# Aeolus_SMA_inc_sensor.net
KiCad netlist of a schematic drawn in EAGLE
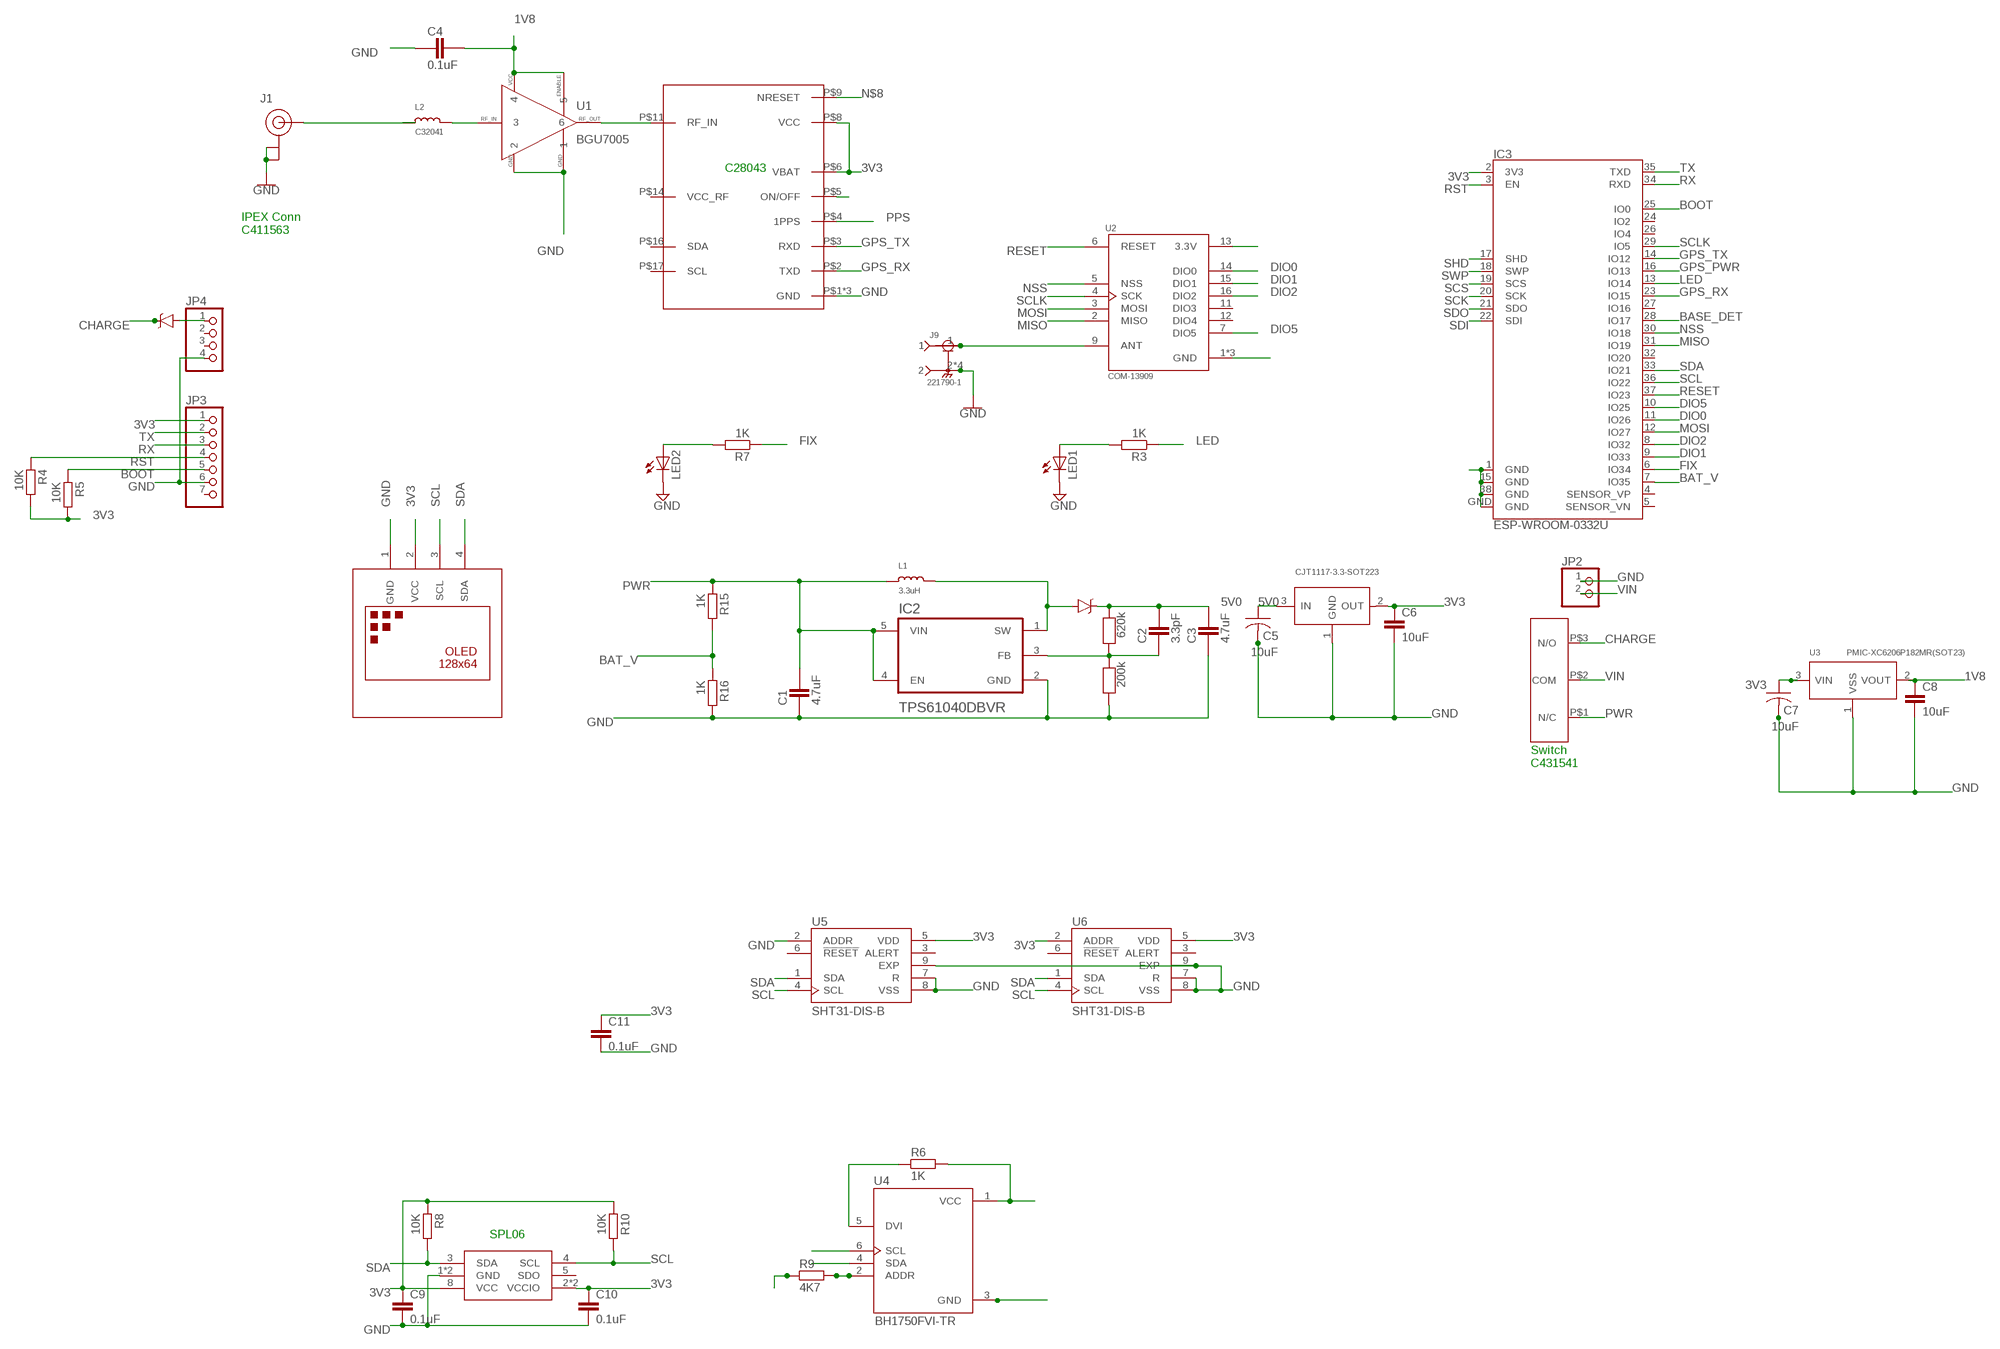
[diagram p0: schematic, sheet 1]

(export (version "E")
  (design (tool "Eeschema 10.0.6"))
  (components
    (comp (ref "C1")
      (value "4.7uF")
      (footprint "eagle-import:CAPC1608X92N")
      (libsource (lib "eagle-import") (part "CAPACITOR_0603"))
    )
    (comp (ref "C2")
      (value "3.3pF")
      (footprint "eagle-import:CAPC1005X60N")
      (libsource (lib "eagle-import") (part "CAPACITOR_0402"))
    )
    (comp (ref "C3")
      (value "4.7uF")
      (footprint "eagle-import:CAPC1608X92N")
      (libsource (lib "eagle-import") (part "CAPACITOR_0603"))
    )
    (comp (ref "C4")
      (value "0.1uF")
      (footprint "eagle-import:CAPC1608X92N")
      (libsource (lib "eagle-import") (part "CAPACITOR_0603"))
    )
    (comp (ref "C5")
      (value "10uF")
      (footprint "eagle-import:C0805")
      (libsource (lib "eagle-import") (part "C-USC0805"))
    )
    (comp (ref "C6")
      (value "10uF")
      (footprint "eagle-import:C0805@1")
      (libsource (lib "eagle-import") (part "C-EUC0805"))
    )
    (comp (ref "C7")
      (value "10uF")
      (footprint "eagle-import:C0402")
      (libsource (lib "eagle-import") (part "C-USC0402"))
    )
    (comp (ref "C8")
      (value "10uF")
      (footprint "eagle-import:C0402K@1")
      (libsource (lib "eagle-import") (part "C-EUC0402K"))
    )
    (comp (ref "C9")
      (value "0.1uF")
      (footprint "eagle-import:C0603@1")
      (libsource (lib "eagle-import") (part "C-EUC0603"))
    )
    (comp (ref "C10")
      (value "0.1uF")
      (footprint "eagle-import:C0603@1")
      (libsource (lib "eagle-import") (part "C-EUC0603"))
    )
    (comp (ref "C11")
      (value "0.1uF")
      (footprint "eagle-import:C0603@1")
      (libsource (lib "eagle-import") (part "C-EUC0603"))
    )
    (comp (ref "D1")
      (value "BA340A")
      (footprint "eagle-import:SMA-DIODE")
      (libsource (lib "eagle-import") (part "B340A"))
    )
    (comp (ref "D2")
      (value "BA340A")
      (footprint "eagle-import:SMA-DIODE")
      (libsource (lib "eagle-import") (part "B340A"))
    )
    (comp (ref "IC1")
      (value "CJT1117-3.3-SOT223")
      (footprint "eagle-import:SOT-223")
      (fields (field (name "MPN") "CJT1117-3.3"))
      (libsource (lib "eagle-import") (part "PMIC-CJT1117-3.3(SOT223)"))
    )
    (comp (ref "IC2")
      (value "TPS61040DBVR")
      (footprint "eagle-import:SOT95P280X145-5N")
      (fields (field (name "MF") "Texas Instruments"))
      (libsource (lib "eagle-import") (part "TPS61040DBVR"))
    )
    (comp (ref "IC3")
      (value "ESP-WROOM-0332U")
      (footprint "eagle-import:ESP32-WROOM-32U")
      (libsource (lib "eagle-import") (part "ESP-WROOM-0332U"))
    )
    (comp (ref "IC54")
      (value "ATGM336H")
      (footprint "eagle-import:ATGM336H")
      (libsource (lib "eagle-import") (part "ATGM336H"))
    )
    (comp (ref "J1")
      (value "U.FL")
      (footprint "eagle-import:U.FL")
      (libsource (lib "eagle-import") (part "U.FL"))
    )
    (comp (ref "J9")
      (value "221790-1")
      (footprint "eagle-import:TE_221790-1")
      (fields (field (name "MF") "TE Connectivity"))
      (libsource (lib "eagle-import") (part "221790-1"))
    )
    (comp (ref "JP2")
      (value "HEADER-1X2ROUND")
      (footprint "eagle-import:1X02_ROUND")
      (libsource (lib "eagle-import") (part "HEADER-1X2ROUND"))
    )
    (comp (ref "JP3")
      (value "HEADER-1X7ROUND")
      (footprint "eagle-import:1X07_ROUND")
      (libsource (lib "eagle-import") (part "HEADER-1X7ROUND"))
    )
    (comp (ref "JP4")
      (value "HEADER-1X4ROUND")
      (footprint "eagle-import:1X04_ROUND")
      (libsource (lib "eagle-import") (part "HEADER-1X4ROUND"))
    )
    (comp (ref "L1")
      (value "3.3uH")
      (footprint "eagle-import:INDUCTOR_5X5MM_NR5040_NOTHERMALS")
      (libsource (lib "eagle-import") (part "INDUCTORNR5040"))
    )
    (comp (ref "L2")
      (value "C32041")
      (footprint "eagle-import:_0402")
      (libsource (lib "eagle-import") (part "INDUCTOR_0402"))
    )
    (comp (ref "LED1")
      (value "LEDSML0805")
      (footprint "eagle-import:SML0805")
      (libsource (lib "eagle-import") (part "LEDSML0805"))
    )
    (comp (ref "LED2")
      (value "LEDSML0805")
      (footprint "eagle-import:SML0805")
      (libsource (lib "eagle-import") (part "LEDSML0805"))
    )
    (comp (ref "R1")
      (value "620k")
      (footprint "eagle-import:0603")
      (libsource (lib "eagle-import") (part "RESISTOR0603"))
    )
    (comp (ref "R2")
      (value "200k")
      (footprint "eagle-import:0603")
      (libsource (lib "eagle-import") (part "RESISTOR0603"))
    )
    (comp (ref "R3")
      (value "1K")
      (footprint "eagle-import:RESC1608X55N")
      (libsource (lib "eagle-import") (part "RESISTOR_0603"))
    )
    (comp (ref "R4")
      (value "10K")
      (footprint "eagle-import:RESC1608X55N")
      (libsource (lib "eagle-import") (part "RESISTOR_0603"))
    )
    (comp (ref "R5")
      (value "10K")
      (footprint "eagle-import:RESC1608X55N")
      (libsource (lib "eagle-import") (part "RESISTOR_0603"))
    )
    (comp (ref "R6")
      (value "1K")
      (footprint "eagle-import:RESC1608X55N")
      (libsource (lib "eagle-import") (part "RESISTOR_0603"))
    )
    (comp (ref "R7")
      (value "1K")
      (footprint "eagle-import:RESC1608X55N")
      (libsource (lib "eagle-import") (part "RESISTOR_0603"))
    )
    (comp (ref "R8")
      (value "10K")
      (footprint "eagle-import:RESC1608X55N")
      (libsource (lib "eagle-import") (part "RESISTOR_0603"))
    )
    (comp (ref "R9")
      (value "4K7")
      (footprint "eagle-import:RESC1608X55N")
      (libsource (lib "eagle-import") (part "RESISTOR_0603"))
    )
    (comp (ref "R10")
      (value "10K")
      (footprint "eagle-import:RESC1608X55N")
      (libsource (lib "eagle-import") (part "RESISTOR_0603"))
    )
    (comp (ref "R15")
      (value "1K")
      (footprint "eagle-import:RESC1608X55N")
      (libsource (lib "eagle-import") (part "RESISTOR_0603"))
    )
    (comp (ref "R16")
      (value "1K")
      (footprint "eagle-import:RESC1608X55N")
      (libsource (lib "eagle-import") (part "RESISTOR_0603"))
    )
    (comp (ref "S1")
      (value "SMD-SWITCH")
      (footprint "eagle-import:SMD-SWITCH")
      (libsource (lib "eagle-import") (part "SMD-SWITCH"))
    )
    (comp (ref "U$1")
      (value "DISPLAY-OLED-128X64-I2C")
      (footprint "eagle-import:DISPLAY-OLED-128X64-I2C")
      (libsource (lib "eagle-import") (part "DISPLAY-OLED-128X64-I2C"))
    )
    (comp (ref "U$4")
      (value "SPL06")
      (footprint "eagle-import:SPL06")
      (libsource (lib "eagle-import") (part "SPL06"))
    )
    (comp (ref "U1")
      (value "BGU7005")
      (footprint "eagle-import:SOT886")
      (fields (field (name "MF") "NXP USA"))
      (libsource (lib "eagle-import") (part "BGU7005"))
    )
    (comp (ref "U2")
      (value "COM-13909")
      (footprint "eagle-import:MOD_COM-13909")
      (fields (field (name "MF") "HOPERF") (field (name "MP") "RFM69HCW-315S2"))
      (libsource (lib "eagle-import") (part "COM-13909"))
    )
    (comp (ref "U3")
      (value "PMIC-XC6206P182MR(SOT23)")
      (footprint "eagle-import:SOT-23")
      (fields (field (name "MF") "Torex") (field (name "MP") "XC6206P182MR"))
      (libsource (lib "eagle-import") (part "PMIC-XC6206P182MR(SOT23)"))
    )
    (comp (ref "U4")
      (value "BH1750FVI-TR")
      (footprint "eagle-import:XDCR_BH1750FVI-TR")
      (fields (field (name "MF") "ROHM Semiconductor"))
      (libsource (lib "eagle-import") (part "BH1750FVI-TR"))
    )
    (comp (ref "U5")
      (value "SHT31-DIS-B")
      (footprint "eagle-import:SON50P250X250X100-9N")
      (fields (field (name "MF") "Sensirion AG"))
      (libsource (lib "eagle-import") (part "SHT31-DIS-B"))
    )
    (comp (ref "U6")
      (value "SHT31-DIS-B")
      (footprint "eagle-import:SON50P250X250X100-9N")
      (fields (field (name "MF") "Sensirion AG"))
      (libsource (lib "eagle-import") (part "SHT31-DIS-B"))
    )
  )
  (nets
    (net (code "1") (name "/1V8") (class "Default")
      (node (ref "C4") (pin "2") (pinfunction "2_2") (pintype "passive"))
      (node (ref "C8") (pin "1") (pinfunction "1_1") (pintype "passive"))
      (node (ref "U1") (pin "4") (pinfunction "4_4") (pintype "bidirectional"))
      (node (ref "U1") (pin "5") (pinfunction "5_5") (pintype "bidirectional"))
      (node (ref "U3") (pin "2") (pinfunction "VOUT_2") (pintype "output"))
    )
    (net (code "2") (name "/3V3") (class "Default")
      (node (ref "C10") (pin "1") (pinfunction "1_1") (pintype "passive"))
      (node (ref "C11") (pin "1") (pinfunction "1_1") (pintype "passive"))
      (node (ref "C6") (pin "1") (pinfunction "1_1") (pintype "passive"))
      (node (ref "C7") (pin "1") (pinfunction "1_1") (pintype "passive"))
      (node (ref "C9") (pin "1") (pinfunction "1_1") (pintype "passive"))
      (node (ref "IC1") (pin "2") (pinfunction "OUT_2") (pintype "bidirectional"))
      (node (ref "IC3") (pin "2") (pinfunction "3V3_2") (pintype "bidirectional"))
      (node (ref "IC54") (pin "P$6") (pinfunction "VBAT_P$6") (pintype "bidirectional"))
      (node (ref "IC54") (pin "P$8") (pinfunction "VCC_P$8") (pintype "bidirectional"))
      (node (ref "JP3") (pin "1") (pinfunction "1_1") (pintype "passive"))
      (node (ref "R10") (pin "1") (pinfunction "1_1") (pintype "passive"))
      (node (ref "R4") (pin "2") (pinfunction "2_2") (pintype "passive"))
      (node (ref "R5") (pin "2") (pinfunction "2_2") (pintype "passive"))
      (node (ref "R6") (pin "2") (pinfunction "2_2") (pintype "passive"))
      (node (ref "R8") (pin "1") (pinfunction "1_1") (pintype "passive"))
      (node (ref "U$1") (pin "2") (pinfunction "VCC_2") (pintype "power_in"))
      (node (ref "U$4") (pin "2") (pinfunction "VCCIO_2") (pintype "bidirectional"))
      (node (ref "U$4") (pin "6") (pinfunction "VCCIO_6") (pintype "bidirectional"))
      (node (ref "U$4") (pin "8") (pinfunction "VCC_8") (pintype "bidirectional"))
      (node (ref "U2") (pin "13") (pinfunction "3.3V_13") (pintype "power_in"))
      (node (ref "U3") (pin "3") (pinfunction "VIN_3") (pintype "input"))
      (node (ref "U4") (pin "1") (pinfunction "VCC_1") (pintype "power_in"))
      (node (ref "U5") (pin "5") (pinfunction "VDD_5") (pintype "power_in"))
      (node (ref "U6") (pin "2") (pinfunction "ADDR_2") (pintype "input"))
      (node (ref "U6") (pin "5") (pinfunction "VDD_5") (pintype "power_in"))
    )
    (net (code "3") (name "/5V0") (class "Default")
      (node (ref "C2") (pin "2") (pinfunction "2_2") (pintype "passive"))
      (node (ref "C3") (pin "2") (pinfunction "2_2") (pintype "passive"))
      (node (ref "C5") (pin "1") (pinfunction "1_1") (pintype "passive"))
      (node (ref "D1") (pin "C") (pinfunction "C_C") (pintype "passive"))
      (node (ref "IC1") (pin "3") (pinfunction "IN_3") (pintype "bidirectional"))
      (node (ref "R1") (pin "1") (pinfunction "1_1") (pintype "passive"))
    )
    (net (code "4") (name "/BASE_DET") (class "Default")
      (node (ref "IC3") (pin "28") (pinfunction "IO17_28") (pintype "bidirectional"))
    )
    (net (code "5") (name "/BAT_V") (class "Default")
      (node (ref "IC3") (pin "7") (pinfunction "IO35_7") (pintype "bidirectional"))
      (node (ref "R15") (pin "2") (pinfunction "2_2") (pintype "passive"))
      (node (ref "R16") (pin "1") (pinfunction "1_1") (pintype "passive"))
    )
    (net (code "6") (name "/BOOT") (class "Default")
      (node (ref "IC3") (pin "25") (pinfunction "IO0_25") (pintype "bidirectional"))
      (node (ref "JP3") (pin "5") (pinfunction "5_5") (pintype "passive"))
      (node (ref "R5") (pin "1") (pinfunction "1_1") (pintype "passive"))
    )
    (net (code "7") (name "/CHARGE") (class "Default")
      (node (ref "D2") (pin "C") (pinfunction "C_C") (pintype "passive"))
      (node (ref "S1") (pin "P$3") (pinfunction "N/O_P$3") (pintype "bidirectional"))
    )
    (net (code "8") (name "/DIO0") (class "Default")
      (node (ref "IC3") (pin "11") (pinfunction "IO26_11") (pintype "bidirectional"))
      (node (ref "U2") (pin "14") (pinfunction "DIO0_14") (pintype "bidirectional"))
    )
    (net (code "9") (name "/DIO1") (class "Default")
      (node (ref "IC3") (pin "9") (pinfunction "IO33_9") (pintype "bidirectional"))
      (node (ref "U2") (pin "15") (pinfunction "DIO1_15") (pintype "bidirectional"))
    )
    (net (code "10") (name "/DIO2") (class "Default")
      (node (ref "IC3") (pin "8") (pinfunction "IO32_8") (pintype "bidirectional"))
      (node (ref "U2") (pin "16") (pinfunction "DIO2_16") (pintype "bidirectional"))
    )
    (net (code "11") (name "/DIO5") (class "Default")
      (node (ref "IC3") (pin "10") (pinfunction "IO25_10") (pintype "bidirectional"))
      (node (ref "U2") (pin "7") (pinfunction "DIO5_7") (pintype "bidirectional"))
    )
    (net (code "12") (name "/FIX") (class "Default")
      (node (ref "IC3") (pin "6") (pinfunction "IO34_6") (pintype "bidirectional"))
      (node (ref "R7") (pin "1") (pinfunction "1_1") (pintype "passive"))
    )
    (net (code "13") (name "/GPS_PWR") (class "Default")
      (node (ref "IC3") (pin "16") (pinfunction "IO13_16") (pintype "bidirectional"))
    )
    (net (code "14") (name "/GPS_RX") (class "Default")
      (node (ref "IC3") (pin "23") (pinfunction "IO15_23") (pintype "bidirectional"))
      (node (ref "IC54") (pin "P$2") (pinfunction "TXD_P$2") (pintype "bidirectional"))
    )
    (net (code "15") (name "/GPS_TX") (class "Default")
      (node (ref "IC3") (pin "14") (pinfunction "IO12_14") (pintype "bidirectional"))
      (node (ref "IC54") (pin "P$3") (pinfunction "RXD_P$3") (pintype "bidirectional"))
    )
    (net (code "16") (name "/LED") (class "Default")
      (node (ref "IC3") (pin "13") (pinfunction "IO14_13") (pintype "bidirectional"))
      (node (ref "R3") (pin "1") (pinfunction "1_1") (pintype "passive"))
    )
    (net (code "17") (name "/MISO") (class "Default")
      (node (ref "IC3") (pin "31") (pinfunction "IO19_31") (pintype "bidirectional"))
      (node (ref "U2") (pin "2") (pinfunction "MISO_2") (pintype "input"))
    )
    (net (code "18") (name "/MOSI") (class "Default")
      (node (ref "IC3") (pin "12") (pinfunction "IO27_12") (pintype "bidirectional"))
      (node (ref "U2") (pin "3") (pinfunction "MOSI_3") (pintype "output"))
    )
    (net (code "19") (name "/N$8") (class "Default")
      (node (ref "IC54") (pin "P$9") (pinfunction "NRESET_P$9") (pintype "bidirectional"))
    )
    (net (code "20") (name "/NSS") (class "Default")
      (node (ref "IC3") (pin "30") (pinfunction "IO18_30") (pintype "bidirectional"))
      (node (ref "U2") (pin "5") (pinfunction "NSS_5") (pintype "input"))
    )
    (net (code "21") (name "/PPS") (class "Default")
      (node (ref "IC54") (pin "P$4") (pinfunction "1PPS_P$4") (pintype "bidirectional"))
    )
    (net (code "22") (name "/PWR") (class "Default")
      (node (ref "C1") (pin "2") (pinfunction "2_2") (pintype "passive"))
      (node (ref "IC2") (pin "4") (pinfunction "EN_4") (pintype "input"))
      (node (ref "IC2") (pin "5") (pinfunction "VIN_5") (pintype "input"))
      (node (ref "L1") (pin "P$1") (pinfunction "1_P$1") (pintype "passive"))
      (node (ref "R15") (pin "1") (pinfunction "1_1") (pintype "passive"))
      (node (ref "S1") (pin "P$1") (pinfunction "N/C_P$1") (pintype "bidirectional"))
    )
    (net (code "23") (name "/RESET") (class "Default")
      (node (ref "IC3") (pin "37") (pinfunction "IO23_37") (pintype "bidirectional"))
      (node (ref "U2") (pin "6") (pinfunction "RESET_6") (pintype "bidirectional"))
    )
    (net (code "24") (name "/RST") (class "Default")
      (node (ref "IC3") (pin "3") (pinfunction "EN_3") (pintype "bidirectional"))
      (node (ref "JP3") (pin "4") (pinfunction "4_4") (pintype "passive"))
      (node (ref "R4") (pin "1") (pinfunction "1_1") (pintype "passive"))
    )
    (net (code "25") (name "/RX") (class "Default")
      (node (ref "IC3") (pin "34") (pinfunction "RXD_34") (pintype "bidirectional"))
      (node (ref "JP3") (pin "3") (pinfunction "3_3") (pintype "passive"))
    )
    (net (code "26") (name "/SCK") (class "Default")
      (node (ref "IC3") (pin "20") (pinfunction "SCK_20") (pintype "bidirectional"))
    )
    (net (code "27") (name "/SCL") (class "Default")
      (node (ref "IC3") (pin "36") (pinfunction "IO22_36") (pintype "bidirectional"))
      (node (ref "R10") (pin "2") (pinfunction "2_2") (pintype "passive"))
      (node (ref "U$1") (pin "3") (pinfunction "SCL_3") (pintype "bidirectional"))
      (node (ref "U$4") (pin "4") (pinfunction "SCL_4") (pintype "bidirectional"))
      (node (ref "U4") (pin "6") (pinfunction "SCL_6") (pintype "input"))
      (node (ref "U5") (pin "4") (pinfunction "SCL_4") (pintype "bidirectional"))
      (node (ref "U6") (pin "4") (pinfunction "SCL_4") (pintype "bidirectional"))
    )
    (net (code "28") (name "/SCLK") (class "Default")
      (node (ref "IC3") (pin "29") (pinfunction "IO5_29") (pintype "bidirectional"))
      (node (ref "U2") (pin "4") (pinfunction "SCK_4") (pintype "input"))
    )
    (net (code "29") (name "/SCS") (class "Default")
      (node (ref "IC3") (pin "19") (pinfunction "SCS_19") (pintype "bidirectional"))
    )
    (net (code "30") (name "/SDA") (class "Default")
      (node (ref "IC3") (pin "33") (pinfunction "IO21_33") (pintype "bidirectional"))
      (node (ref "R8") (pin "2") (pinfunction "2_2") (pintype "passive"))
      (node (ref "U$1") (pin "4") (pinfunction "SDA_4") (pintype "bidirectional"))
      (node (ref "U$4") (pin "3") (pinfunction "SDA_3") (pintype "bidirectional"))
      (node (ref "U4") (pin "4") (pinfunction "SDA_4") (pintype "bidirectional"))
      (node (ref "U5") (pin "1") (pinfunction "SDA_1") (pintype "bidirectional"))
      (node (ref "U6") (pin "1") (pinfunction "SDA_1") (pintype "bidirectional"))
    )
    (net (code "31") (name "/SDI") (class "Default")
      (node (ref "IC3") (pin "22") (pinfunction "SDI_22") (pintype "bidirectional"))
    )
    (net (code "32") (name "/SDO") (class "Default")
      (node (ref "IC3") (pin "21") (pinfunction "SDO_21") (pintype "bidirectional"))
    )
    (net (code "33") (name "/SHD") (class "Default")
      (node (ref "IC3") (pin "17") (pinfunction "SHD_17") (pintype "bidirectional"))
    )
    (net (code "34") (name "/SWP") (class "Default")
      (node (ref "IC3") (pin "18") (pinfunction "SWP_18") (pintype "bidirectional"))
    )
    (net (code "35") (name "/TX") (class "Default")
      (node (ref "IC3") (pin "35") (pinfunction "TXD_35") (pintype "bidirectional"))
      (node (ref "JP3") (pin "2") (pinfunction "2_2") (pintype "passive"))
    )
    (net (code "36") (name "/VIN") (class "Default")
      (node (ref "JP2") (pin "2") (pinfunction "2_2") (pintype "passive"))
      (node (ref "S1") (pin "P$2") (pinfunction "COM_P$2") (pintype "bidirectional"))
    )
    (net (code "37") (name "GND") (class "Default")
      (node (ref "C1") (pin "1") (pinfunction "1_1") (pintype "passive"))
      (node (ref "C10") (pin "2") (pinfunction "2_2") (pintype "passive"))
      (node (ref "C11") (pin "2") (pinfunction "2_2") (pintype "passive"))
      (node (ref "C3") (pin "1") (pinfunction "1_1") (pintype "passive"))
      (node (ref "C4") (pin "1") (pinfunction "1_1") (pintype "passive"))
      (node (ref "C5") (pin "2") (pinfunction "2_2") (pintype "passive"))
      (node (ref "C6") (pin "2") (pinfunction "2_2") (pintype "passive"))
      (node (ref "C7") (pin "2") (pinfunction "2_2") (pintype "passive"))
      (node (ref "C8") (pin "2") (pinfunction "2_2") (pintype "passive"))
      (node (ref "C9") (pin "2") (pinfunction "2_2") (pintype "passive"))
      (node (ref "IC1") (pin "1") (pinfunction "GND_1") (pintype "bidirectional"))
      (node (ref "IC2") (pin "2") (pinfunction "GND_2") (pintype "power_in"))
      (node (ref "IC3") (pin "1") (pinfunction "GND_1") (pintype "bidirectional"))
      (node (ref "IC3") (pin "15") (pinfunction "GND_15") (pintype "bidirectional"))
      (node (ref "IC3") (pin "38") (pinfunction "GND_38") (pintype "bidirectional"))
      (node (ref "IC3") (pin "GND") (pinfunction "GND_GND") (pintype "bidirectional"))
      (node (ref "IC54") (pin "P$1") (pinfunction "GND_P$1") (pintype "bidirectional"))
      (node (ref "IC54") (pin "P$10") (pinfunction "GND_P$10") (pintype "bidirectional"))
      (node (ref "IC54") (pin "P$12") (pinfunction "GND_P$12") (pintype "bidirectional"))
      (node (ref "J1") (pin "1") (pinfunction "GND_1") (pintype "bidirectional"))
      (node (ref "J1") (pin "2") (pinfunction "GND_2") (pintype "bidirectional"))
      (node (ref "J9") (pin "2") (pinfunction "2_2") (pintype "passive"))
      (node (ref "J9") (pin "3") (pinfunction "2_3") (pintype "passive"))
      (node (ref "J9") (pin "4") (pinfunction "2_4") (pintype "passive"))
      (node (ref "J9") (pin "5") (pinfunction "2_5") (pintype "passive"))
      (node (ref "JP2") (pin "1") (pinfunction "1_1") (pintype "passive"))
      (node (ref "JP3") (pin "6") (pinfunction "6_6") (pintype "passive"))
      (node (ref "JP4") (pin "4") (pinfunction "4_4") (pintype "passive"))
      (node (ref "LED1") (pin "C") (pinfunction "C_C") (pintype "passive"))
      (node (ref "LED2") (pin "C") (pinfunction "C_C") (pintype "passive"))
      (node (ref "R16") (pin "2") (pinfunction "2_2") (pintype "passive"))
      (node (ref "R2") (pin "2") (pinfunction "2_2") (pintype "passive"))
      (node (ref "R9") (pin "1") (pinfunction "1_1") (pintype "passive"))
      (node (ref "U$1") (pin "1") (pinfunction "GND_1") (pintype "power_in"))
      (node (ref "U$4") (pin "1") (pinfunction "GND_1") (pintype "bidirectional"))
      (node (ref "U$4") (pin "7") (pinfunction "GND_7") (pintype "bidirectional"))
      (node (ref "U1") (pin "1") (pinfunction "1_1") (pintype "bidirectional"))
      (node (ref "U1") (pin "2") (pinfunction "2_2") (pintype "bidirectional"))
      (node (ref "U2") (pin "1") (pinfunction "GND_1") (pintype "power_in"))
      (node (ref "U2") (pin "10") (pinfunction "GND_10") (pintype "power_in"))
      (node (ref "U2") (pin "8") (pinfunction "GND_8") (pintype "power_in"))
      (node (ref "U3") (pin "1") (pinfunction "VSS_1") (pintype "power_in"))
      (node (ref "U4") (pin "3") (pinfunction "GND_3") (pintype "power_in"))
      (node (ref "U5") (pin "2") (pinfunction "ADDR_2") (pintype "input"))
      (node (ref "U5") (pin "7") (pinfunction "R_7") (pintype "power_in"))
      (node (ref "U5") (pin "8") (pinfunction "VSS_8") (pintype "power_in"))
      (node (ref "U5") (pin "9") (pinfunction "EXP_9") (pintype "power_in"))
      (node (ref "U6") (pin "7") (pinfunction "R_7") (pintype "power_in"))
      (node (ref "U6") (pin "8") (pinfunction "VSS_8") (pintype "power_in"))
      (node (ref "U6") (pin "9") (pinfunction "EXP_9") (pintype "power_in"))
    )
    (net (code "38") (name "Net-(D2-PadA)") (class "Default")
      (node (ref "D2") (pin "A") (pinfunction "A_A") (pintype "passive"))
      (node (ref "JP4") (pin "1") (pinfunction "1_1") (pintype "passive"))
    )
    (net (code "39") (name "Net-(IC2-FB)") (class "Default")
      (node (ref "C2") (pin "1") (pinfunction "1_1") (pintype "passive"))
      (node (ref "IC2") (pin "3") (pinfunction "FB_3") (pintype "input"))
      (node (ref "R1") (pin "2") (pinfunction "2_2") (pintype "passive"))
      (node (ref "R2") (pin "1") (pinfunction "1_1") (pintype "passive"))
    )
    (net (code "40") (name "Net-(IC2-SW)") (class "Default")
      (node (ref "D1") (pin "A") (pinfunction "A_A") (pintype "passive"))
      (node (ref "IC2") (pin "1") (pinfunction "SW_1") (pintype "bidirectional"))
      (node (ref "L1") (pin "P$2") (pinfunction "2_P$2") (pintype "passive"))
    )
    (net (code "41") (name "Net-(IC54-RF_IN)") (class "Default")
      (node (ref "IC54") (pin "P$11") (pinfunction "RF_IN_P$11") (pintype "bidirectional"))
      (node (ref "U1") (pin "6") (pinfunction "6_6") (pintype "bidirectional"))
    )
    (net (code "42") (name "Net-(J1-SIGNAL)") (class "Default")
      (node (ref "J1") (pin "FEED") (pinfunction "SIGNAL_FEED") (pintype "bidirectional"))
      (node (ref "L2") (pin "1") (pinfunction "1_1") (pintype "passive"))
    )
    (net (code "43") (name "Net-(L2-Pad2)") (class "Default")
      (node (ref "L2") (pin "2") (pinfunction "2_2") (pintype "passive"))
      (node (ref "U1") (pin "3") (pinfunction "3_3") (pintype "bidirectional"))
    )
    (net (code "44") (name "Net-(LED1-PadA)") (class "Default")
      (node (ref "LED1") (pin "A") (pinfunction "A_A") (pintype "passive"))
      (node (ref "R3") (pin "2") (pinfunction "2_2") (pintype "passive"))
    )
    (net (code "45") (name "Net-(LED2-PadA)") (class "Default")
      (node (ref "LED2") (pin "A") (pinfunction "A_A") (pintype "passive"))
      (node (ref "R7") (pin "2") (pinfunction "2_2") (pintype "passive"))
    )
    (net (code "46") (name "Net-(U2-ANT)") (class "Default")
      (node (ref "J9") (pin "1") (pinfunction "1_1") (pintype "passive"))
      (node (ref "U2") (pin "9") (pinfunction "ANT_9") (pintype "bidirectional"))
    )
    (net (code "47") (name "Net-(U4-ADDR)") (class "Default")
      (node (ref "R9") (pin "2") (pinfunction "2_2") (pintype "passive"))
      (node (ref "U4") (pin "2") (pinfunction "ADDR_2") (pintype "input"))
    )
    (net (code "48") (name "Net-(U4-DVI)") (class "Default")
      (node (ref "R6") (pin "1") (pinfunction "1_1") (pintype "passive"))
      (node (ref "U4") (pin "5") (pinfunction "DVI_5") (pintype "input"))
    )
    (net (code "49") (name "unconnected-(IC3-IO2-Pad24)") (class "Default")
      (node (ref "IC3") (pin "24") (pinfunction "IO2_24") (pintype "bidirectional"))
    )
    (net (code "50") (name "unconnected-(IC3-IO4-Pad26)") (class "Default")
      (node (ref "IC3") (pin "26") (pinfunction "IO4_26") (pintype "bidirectional"))
    )
    (net (code "51") (name "unconnected-(IC3-IO16-Pad27)") (class "Default")
      (node (ref "IC3") (pin "27") (pinfunction "IO16_27") (pintype "bidirectional"))
    )
    (net (code "52") (name "unconnected-(IC3-IO20-Pad32)") (class "Default")
      (node (ref "IC3") (pin "32") (pinfunction "IO20_32") (pintype "bidirectional"))
    )
    (net (code "53") (name "unconnected-(IC3-SENSOR_VN-Pad5)") (class "Default")
      (node (ref "IC3") (pin "5") (pinfunction "SENSOR_VN_5") (pintype "bidirectional"))
    )
    (net (code "54") (name "unconnected-(IC3-SENSOR_VP-Pad4)") (class "Default")
      (node (ref "IC3") (pin "4") (pinfunction "SENSOR_VP_4") (pintype "bidirectional"))
    )
    (net (code "55") (name "unconnected-(IC54-ON{slash}OFF-PadP$5)") (class "Default")
      (node (ref "IC54") (pin "P$5") (pinfunction "ON/OFF_P$5") (pintype "bidirectional"))
    )
    (net (code "56") (name "unconnected-(IC54-SCL-PadP$17)") (class "Default")
      (node (ref "IC54") (pin "P$17") (pinfunction "SCL_P$17") (pintype "bidirectional"))
    )
    (net (code "57") (name "unconnected-(IC54-SDA-PadP$16)") (class "Default")
      (node (ref "IC54") (pin "P$16") (pinfunction "SDA_P$16") (pintype "bidirectional"))
    )
    (net (code "58") (name "unconnected-(IC54-VCC_RF-PadP$14)") (class "Default")
      (node (ref "IC54") (pin "P$14") (pinfunction "VCC_RF_P$14") (pintype "bidirectional"))
    )
    (net (code "59") (name "unconnected-(JP3-Pad7)") (class "Default")
      (node (ref "JP3") (pin "7") (pinfunction "7_7") (pintype "passive"))
    )
    (net (code "60") (name "unconnected-(JP4-Pad2)") (class "Default")
      (node (ref "JP4") (pin "2") (pinfunction "2_2") (pintype "passive"))
    )
    (net (code "61") (name "unconnected-(JP4-Pad3)") (class "Default")
      (node (ref "JP4") (pin "3") (pinfunction "3_3") (pintype "passive"))
    )
    (net (code "62") (name "unconnected-(U$4-SDO-Pad5)") (class "Default")
      (node (ref "U$4") (pin "5") (pinfunction "SDO_5") (pintype "bidirectional"))
    )
    (net (code "63") (name "unconnected-(U2-DIO3-Pad11)") (class "Default")
      (node (ref "U2") (pin "11") (pinfunction "DIO3_11") (pintype "bidirectional"))
    )
    (net (code "64") (name "unconnected-(U2-DIO4-Pad12)") (class "Default")
      (node (ref "U2") (pin "12") (pinfunction "DIO4_12") (pintype "bidirectional"))
    )
    (net (code "65") (name "unconnected-(U5-ALERT-Pad3)") (class "Default")
      (node (ref "U5") (pin "3") (pinfunction "ALERT_3") (pintype "output"))
    )
    (net (code "66") (name "unconnected-(U5-~{RESET}-Pad6)") (class "Default")
      (node (ref "U5") (pin "6") (pinfunction "~{RESET}_6") (pintype "input"))
    )
    (net (code "67") (name "unconnected-(U6-ALERT-Pad3)") (class "Default")
      (node (ref "U6") (pin "3") (pinfunction "ALERT_3") (pintype "output"))
    )
    (net (code "68") (name "unconnected-(U6-~{RESET}-Pad6)") (class "Default")
      (node (ref "U6") (pin "6") (pinfunction "~{RESET}_6") (pintype "input"))
    )
  )
)
